# HVBoard.net
KiCad netlist of a schematic drawn in EAGLE
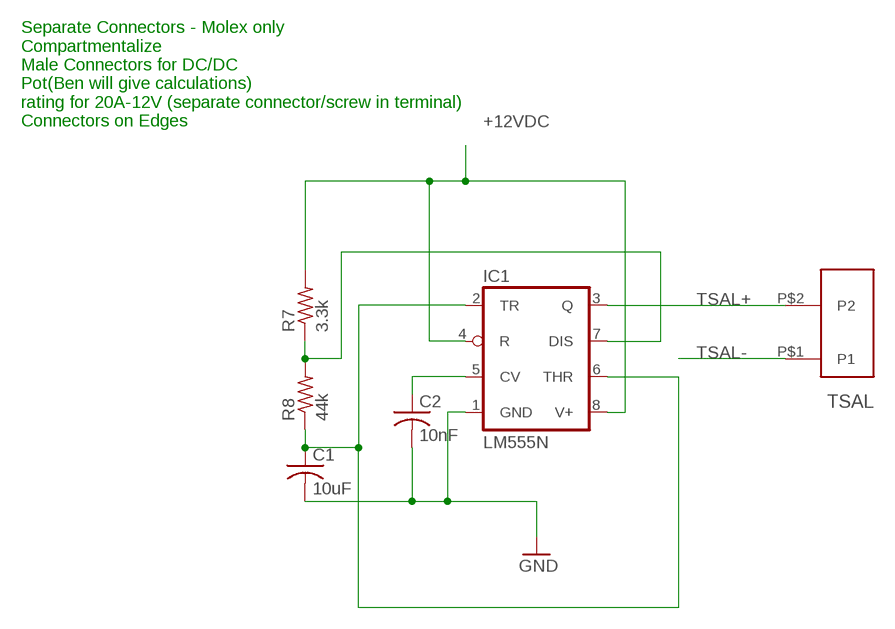
[diagram p0: schematic, sheet 1]
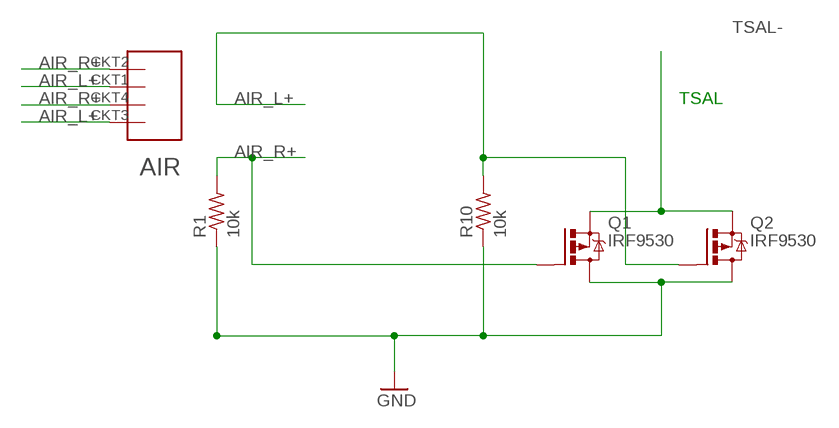
[diagram p1: schematic, sheet 2]
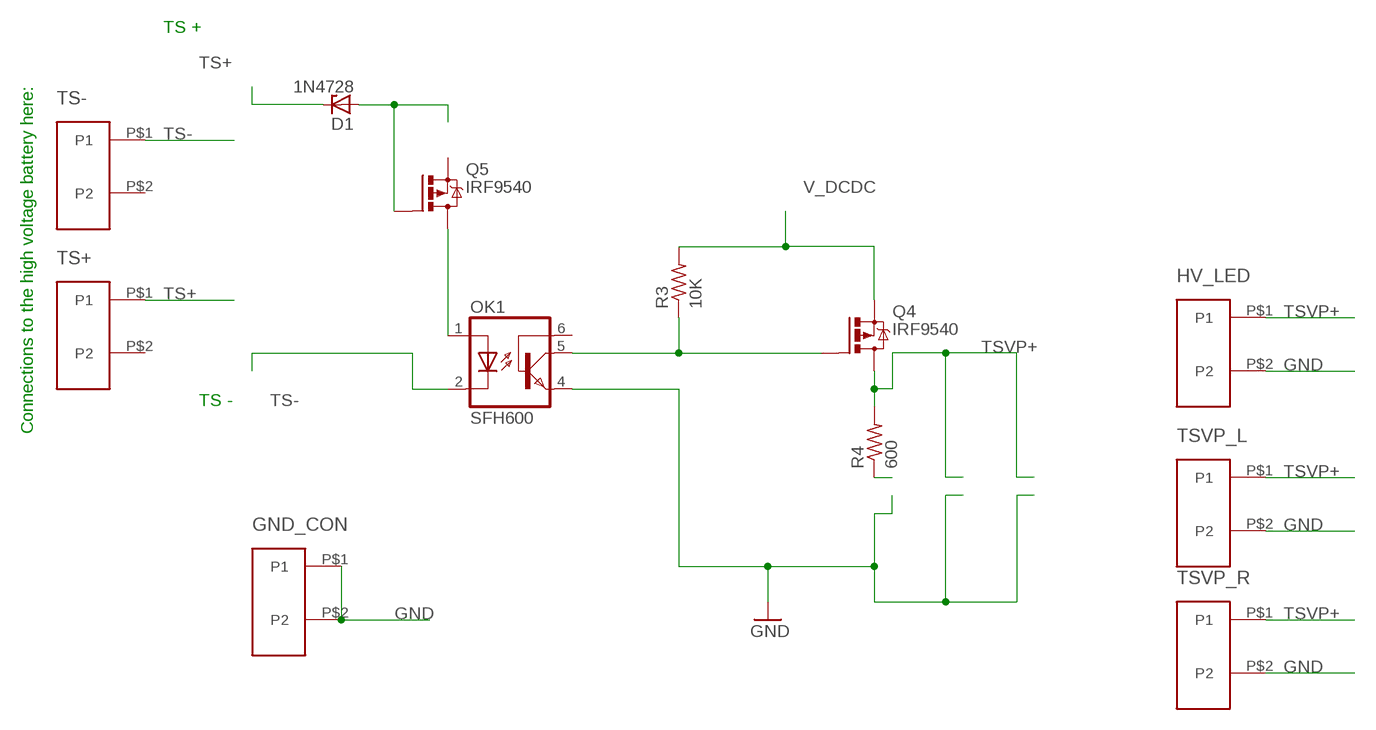
[diagram p2: schematic, sheet 3]
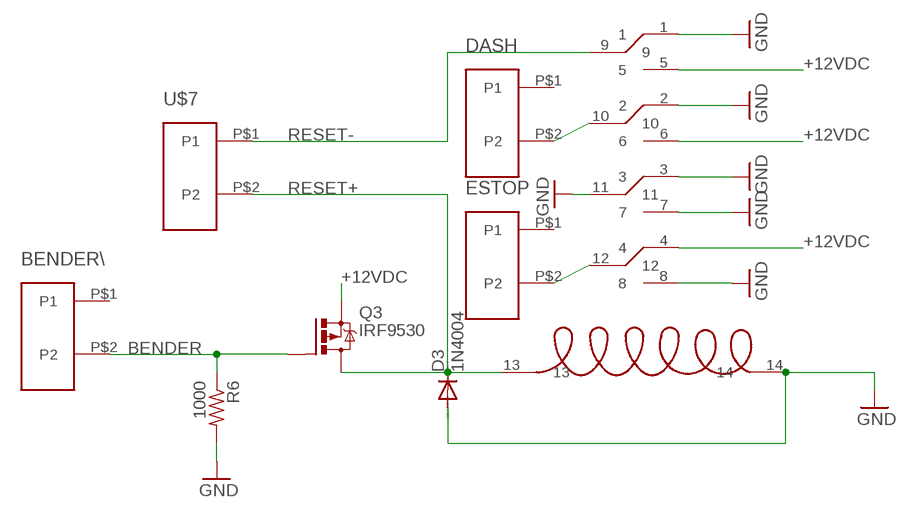
[diagram p3: schematic, sheet 4]
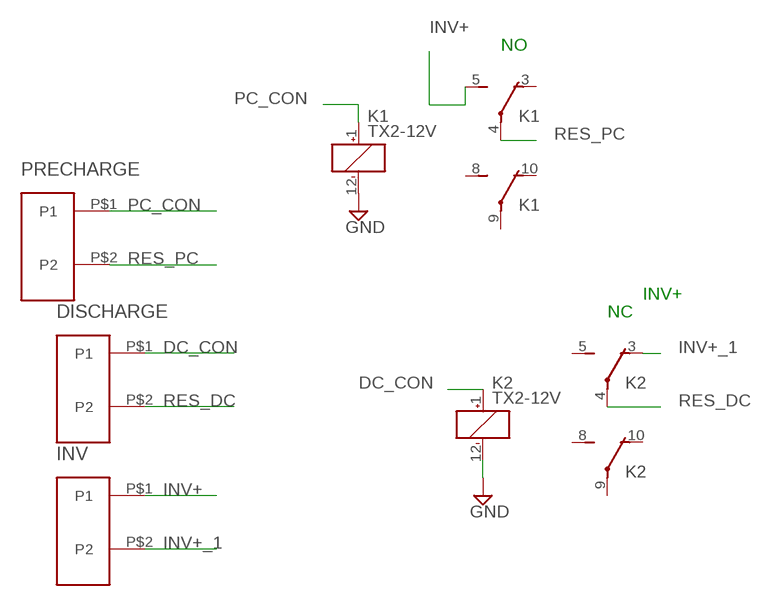
[diagram p4: schematic, sheet 5]
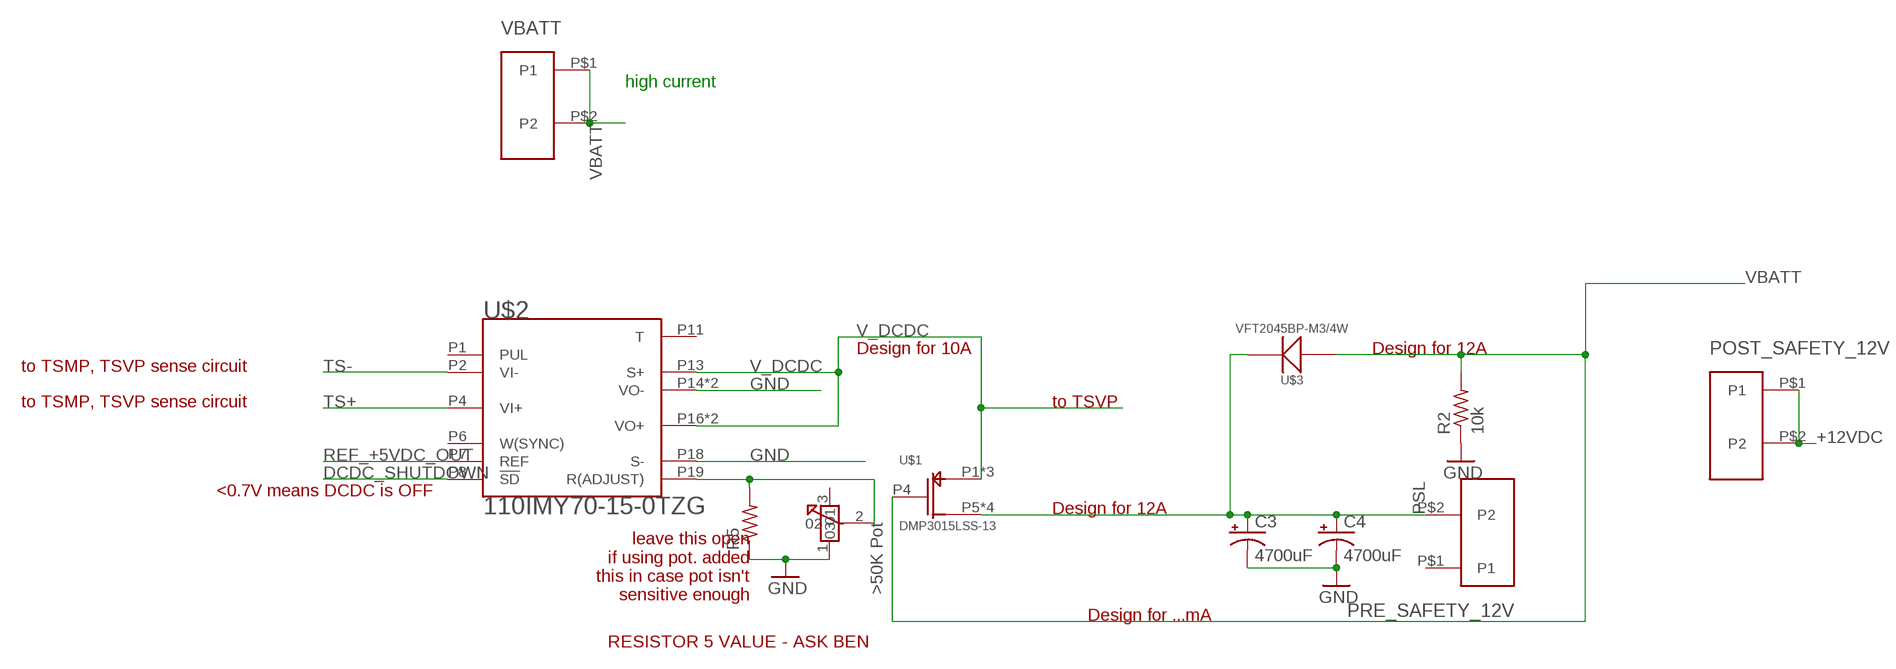
[diagram p5: schematic, sheet 6]

(export (version "E")
  (design (tool "Eeschema 10.0.6"))
  (components
    (comp (ref "BENDER\\")
      (value "MINIFIT_2PIN")
      (footprint "eagle-import:2PIN_MOLEXMINIFIT")
      (libsource (lib "eagle-import") (part "MINIFIT_2PIN"))
    )
    (comp (ref "D3")
      (value "1N4004")
      (footprint "eagle-import:DO41-10")
      (libsource (lib "eagle-import") (part "1N4004"))
    )
    (comp (ref "DASH")
      (value "MINIFIT_2PIN")
      (footprint "eagle-import:2PIN_MOLEXMINIFIT")
      (libsource (lib "eagle-import") (part "MINIFIT_2PIN"))
    )
    (comp (ref "ESTOP")
      (value "MINIFIT_2PIN")
      (footprint "eagle-import:2PIN_MOLEXMINIFIT")
      (libsource (lib "eagle-import") (part "MINIFIT_2PIN"))
    )
    (comp (ref "NEW??1")
      (value "HJ4-DC12VHJ4-DC12V")
      (footprint "eagle-import:HJ4-DC12V")
      (libsource (lib "eagle-import") (part "HJ4-DC12VHJ4-DC12V"))
    )
    (comp (ref "Q3")
      (value "IRF9530")
      (footprint "eagle-import:TO220BV")
      (libsource (lib "eagle-import") (part "IRF9530"))
    )
    (comp (ref "R6")
      (value "1000")
      (footprint "eagle-import:M5923")
      (libsource (lib "eagle-import") (part "R-US_M5923"))
    )
    (comp (ref "U$7")
      (value "MINIFIT_2PIN")
      (footprint "eagle-import:2PIN_MOLEXMINIFIT")
      (libsource (lib "eagle-import") (part "MINIFIT_2PIN"))
    )
    (comp (ref "DISCHARGE")
      (value "MINIFIT_2PIN")
      (footprint "eagle-import:2PIN_MOLEXMINIFIT")
      (libsource (lib "eagle-import") (part "MINIFIT_2PIN"))
    )
    (comp (ref "INV")
      (value "MINIFIT_2PIN")
      (footprint "eagle-import:2PIN_MOLEXMINIFIT")
      (libsource (lib "eagle-import") (part "MINIFIT_2PIN"))
    )
    (comp (ref "K1")
      (value "TX2-12V")
      (footprint "eagle-import:TX2")
      (fields (field (name "MF") "AROMAT/ MATSUSHITA"))
      (libsource (lib "eagle-import") (part "TX2?-12V"))
    )
    (comp (ref "K2")
      (value "TX2-12V")
      (footprint "eagle-import:TX2")
      (fields (field (name "MF") "AROMAT/ MATSUSHITA"))
      (libsource (lib "eagle-import") (part "TX2?-12V"))
    )
    (comp (ref "PRECHARGE")
      (value "MINIFIT_2PIN")
      (footprint "eagle-import:2PIN_MOLEXMINIFIT")
      (libsource (lib "eagle-import") (part "MINIFIT_2PIN"))
    )
    (comp (ref "C3")
      (value "4700uF")
      (footprint "eagle-import:CPOL-RADIAL-1000UF-63V")
      (libsource (lib "eagle-import") (part "CAP_POLPTH3"))
    )
    (comp (ref "C4")
      (value "4700uF")
      (footprint "eagle-import:CPOL-RADIAL-1000UF-63V")
      (libsource (lib "eagle-import") (part "CAP_POLPTH3"))
    )
    (comp (ref "POST_SAFETY_12V")
      (value "MINIFIT_2PIN")
      (footprint "eagle-import:2PIN_MOLEXMINIFIT")
      (libsource (lib "eagle-import") (part "MINIFIT_2PIN"))
    )
    (comp (ref "POT1")
      (value "3310P-001-503L-NP")
      (footprint "eagle-import:3310P-001-503L-NP")
      (libsource (lib "eagle-import") (part "3310P-001-503L-NP"))
    )
    (comp (ref "PRE_SAFETY_12V")
      (value "MINIFIT_2PIN")
      (footprint "eagle-import:2PIN_MOLEXMINIFIT")
      (libsource (lib "eagle-import") (part "MINIFIT_2PIN"))
    )
    (comp (ref "R2")
      (value "10k")
      (footprint "eagle-import:R0603")
      (libsource (lib "eagle-import") (part "resistor_R-US_R0603"))
    )
    (comp (ref "R5")
      (value "R-US_R0805")
      (footprint "eagle-import:R0805")
      (libsource (lib "eagle-import") (part "R-US_R0805"))
    )
    (comp (ref "U$1")
      (value "DMP3015LSS-13")
      (footprint "eagle-import:8-SOP")
      (fields (field (name "MANUFACTURER") "Diodes Incorporated"))
      (libsource (lib "eagle-import") (part "DMP3015LSS-13"))
    )
    (comp (ref "U$2")
      (value "110IMY70-15-0TZG")
      (footprint "eagle-import:110IMY70-15-0TZG")
      (libsource (lib "eagle-import") (part "110IMY70-15-0TZG"))
    )
    (comp (ref "U$3")
      (value "VFT2045BP-M3/4W")
      (footprint "eagle-import:VFT2045BP-M3_4W")
      (fields (field (name "MANUFACTURER") "Vishay Semiconductor Diodes Division"))
      (libsource (lib "eagle-import") (part "VFT2045BP-M3/4W"))
    )
    (comp (ref "VBATT")
      (value "MINIFIT_2PIN")
      (footprint "eagle-import:2PIN_MOLEXMINIFIT")
      (libsource (lib "eagle-import") (part "MINIFIT_2PIN"))
    )
    (comp (ref "C1")
      (value "10uF")
      (footprint "eagle-import:C025-025X050")
      (libsource (lib "eagle-import") (part "C-US025-025X050"))
    )
    (comp (ref "C2")
      (value "10nF")
      (footprint "eagle-import:C025-025X050")
      (libsource (lib "eagle-import") (part "C-US025-025X050"))
    )
    (comp (ref "IC1")
      (value "LM555N")
      (footprint "eagle-import:DIL08")
      (libsource (lib "eagle-import") (part "555NLM"))
    )
    (comp (ref "R7")
      (value "3.3k")
      (footprint "eagle-import:0207_7")
      (libsource (lib "eagle-import") (part "R-US_0207/7"))
    )
    (comp (ref "R8")
      (value "44k")
      (footprint "eagle-import:0207_7")
      (libsource (lib "eagle-import") (part "R-US_0207/7"))
    )
    (comp (ref "TSAL")
      (value "MINIFIT_2PIN")
      (footprint "eagle-import:2PIN_MOLEXMINIFIT")
      (libsource (lib "eagle-import") (part "MINIFIT_2PIN"))
    )
    (comp (ref "D1")
      (value "1N4728")
      (footprint "eagle-import:DO41Z10")
      (libsource (lib "eagle-import") (part "1N4728"))
    )
    (comp (ref "GND_CON")
      (value "MINIFIT_2PIN")
      (footprint "eagle-import:2PIN_MOLEXMINIFIT")
      (libsource (lib "eagle-import") (part "MINIFIT_2PIN"))
    )
    (comp (ref "HV_LED")
      (value "MINIFIT_2PIN")
      (footprint "eagle-import:2PIN_MOLEXMINIFIT")
      (libsource (lib "eagle-import") (part "MINIFIT_2PIN"))
    )
    (comp (ref "OK1")
      (value "SFH600")
      (footprint "eagle-import:DIL06")
      (fields (field (name "MF") "VISHAY/TELEFUNKEN") (field (name "MPN") "SFH600-1"))
      (libsource (lib "eagle-import") (part "SFH600"))
    )
    (comp (ref "Q4")
      (value "IRF9540")
      (footprint "eagle-import:TO220BV")
      (libsource (lib "eagle-import") (part "IRF9530"))
    )
    (comp (ref "Q5")
      (value "IRF9540")
      (footprint "eagle-import:TO220BV")
      (libsource (lib "eagle-import") (part "IRF9530"))
    )
    (comp (ref "R3")
      (value "10K")
      (footprint "eagle-import:R0603")
      (libsource (lib "eagle-import") (part "resistor_R-US_R0603"))
    )
    (comp (ref "R4")
      (value "600")
      (footprint "eagle-import:R0603")
      (libsource (lib "eagle-import") (part "resistor_R-US_R0603"))
    )
    (comp (ref "TS+")
      (value "MINIFIT_2PIN")
      (footprint "eagle-import:2PIN_MOLEXMINIFIT")
      (libsource (lib "eagle-import") (part "MINIFIT_2PIN"))
    )
    (comp (ref "TS-")
      (value "MINIFIT_2PIN")
      (footprint "eagle-import:2PIN_MOLEXMINIFIT")
      (libsource (lib "eagle-import") (part "MINIFIT_2PIN"))
    )
    (comp (ref "TSVP_L")
      (value "MINIFIT_2PIN")
      (footprint "eagle-import:2PIN_MOLEXMINIFIT")
      (libsource (lib "eagle-import") (part "MINIFIT_2PIN"))
    )
    (comp (ref "TSVP_R")
      (value "MINIFIT_2PIN")
      (footprint "eagle-import:2PIN_MOLEXMINIFIT")
      (libsource (lib "eagle-import") (part "MINIFIT_2PIN"))
    )
    (comp (ref "AIR")
      (value "MHYBRIDMOLEX")
      (footprint "eagle-import:MOLEXMINIFIT6")
      (libsource (lib "eagle-import") (part "MHYBRIDMOLEX"))
    )
    (comp (ref "Q1")
      (value "IRF9530")
      (footprint "eagle-import:TO220BV")
      (libsource (lib "eagle-import") (part "IRF9530"))
    )
    (comp (ref "Q2")
      (value "IRF9530")
      (footprint "eagle-import:TO220BV")
      (libsource (lib "eagle-import") (part "IRF9530"))
    )
    (comp (ref "R1")
      (value "10k")
      (footprint "eagle-import:0207_7")
      (libsource (lib "eagle-import") (part "R-US_0207/7"))
    )
    (comp (ref "R10")
      (value "10k")
      (footprint "eagle-import:0207_7")
      (libsource (lib "eagle-import") (part "R-US_0207/7"))
    )
  )
  (nets
    (net (code "1") (name "+12VDC") (class "Default")
      (node (ref "IC1") (pin "4") (pinfunction "R_4") (pintype "input"))
      (node (ref "IC1") (pin "8") (pinfunction "V+_8") (pintype "power_in"))
      (node (ref "NEW??1") (pin "4") (pinfunction "4_4") (pintype "bidirectional"))
      (node (ref "NEW??1") (pin "5") (pinfunction "5_5") (pintype "bidirectional"))
      (node (ref "NEW??1") (pin "6") (pinfunction "6_6") (pintype "bidirectional"))
      (node (ref "POST_SAFETY_12V") (pin "P$1") (pinfunction "P1_P$1") (pintype "bidirectional"))
      (node (ref "POST_SAFETY_12V") (pin "P$2") (pinfunction "P2_P$2") (pintype "bidirectional"))
      (node (ref "Q3") (pin "S") (pinfunction "S_S") (pintype "passive"))
      (node (ref "R7") (pin "2") (pinfunction "2_2") (pintype "passive"))
    )
    (net (code "2") (name "AIR_L+") (class "Default")
      (node (ref "AIR") (pin "CKT1") (pinfunction "GND_CKT1") (pintype "bidirectional"))
      (node (ref "AIR") (pin "CKT3") (pinfunction "V_IN(12)_CKT3") (pintype "bidirectional"))
      (node (ref "Q2") (pin "G") (pinfunction "G_G") (pintype "passive"))
      (node (ref "R10") (pin "2") (pinfunction "2_2") (pintype "passive"))
    )
    (net (code "3") (name "AIR_R+") (class "Default")
      (node (ref "AIR") (pin "CKT2") (pinfunction "GND2_CKT2") (pintype "bidirectional"))
      (node (ref "AIR") (pin "CKT4") (pinfunction "V_IN2(12)_CKT4") (pintype "bidirectional"))
      (node (ref "Q1") (pin "G") (pinfunction "G_G") (pintype "passive"))
      (node (ref "R1") (pin "2") (pinfunction "2_2") (pintype "passive"))
    )
    (net (code "4") (name "BENDER") (class "Default")
      (node (ref "BENDER\\") (pin "P$2") (pinfunction "P2_P$2") (pintype "bidirectional"))
      (node (ref "Q3") (pin "G") (pinfunction "G_G") (pintype "passive"))
      (node (ref "R6") (pin "1") (pinfunction "1_1") (pintype "passive"))
    )
    (net (code "5") (name "DCDC_SHUTDOWN") (class "Default")
      (node (ref "U$2") (pin "P8") (pinfunction "~{SD}_P8") (pintype "bidirectional"))
    )
    (net (code "6") (name "DC_CON") (class "Default")
      (node (ref "DISCHARGE") (pin "P$1") (pinfunction "P1_P$1") (pintype "bidirectional"))
      (node (ref "K2") (pin "1") (pinfunction "+_1") (pintype "passive"))
    )
    (net (code "7") (name "GND") (class "Default")
      (node (ref "C1") (pin "2") (pinfunction "2_2") (pintype "passive"))
      (node (ref "C2") (pin "2") (pinfunction "2_2") (pintype "passive"))
      (node (ref "C3") (pin "2") (pinfunction "-_2") (pintype "passive"))
      (node (ref "C4") (pin "2") (pinfunction "-_2") (pintype "passive"))
      (node (ref "D3") (pin "A") (pinfunction "A_A") (pintype "passive"))
      (node (ref "GND_CON") (pin "P$1") (pinfunction "P1_P$1") (pintype "bidirectional"))
      (node (ref "GND_CON") (pin "P$2") (pinfunction "P2_P$2") (pintype "bidirectional"))
      (node (ref "HV_LED") (pin "P$2") (pinfunction "P2_P$2") (pintype "bidirectional"))
      (node (ref "IC1") (pin "1") (pinfunction "GND_1") (pintype "power_in"))
      (node (ref "K1") (pin "12") (pinfunction "-_12") (pintype "passive"))
      (node (ref "K2") (pin "12") (pinfunction "-_12") (pintype "passive"))
      (node (ref "NEW??1") (pin "1") (pinfunction "1_1") (pintype "bidirectional"))
      (node (ref "NEW??1") (pin "11") (pinfunction "11_11") (pintype "bidirectional"))
      (node (ref "NEW??1") (pin "14") (pinfunction "14_14") (pintype "bidirectional"))
      (node (ref "NEW??1") (pin "2") (pinfunction "2_2") (pintype "bidirectional"))
      (node (ref "NEW??1") (pin "3") (pinfunction "3_3") (pintype "bidirectional"))
      (node (ref "NEW??1") (pin "7") (pinfunction "7_7") (pintype "bidirectional"))
      (node (ref "NEW??1") (pin "8") (pinfunction "8_8") (pintype "bidirectional"))
      (node (ref "OK1") (pin "4") (pinfunction "EMI_4") (pintype "passive"))
      (node (ref "POT1") (pin "1") (pinfunction "01_1") (pintype "bidirectional"))
      (node (ref "Q1") (pin "D") (pinfunction "D_D") (pintype "passive"))
      (node (ref "Q2") (pin "D") (pinfunction "D_D") (pintype "passive"))
      (node (ref "R1") (pin "1") (pinfunction "1_1") (pintype "passive"))
      (node (ref "R10") (pin "1") (pinfunction "1_1") (pintype "passive"))
      (node (ref "R2") (pin "1") (pinfunction "1_1") (pintype "passive"))
      (node (ref "R5") (pin "1") (pinfunction "1_1") (pintype "passive"))
      (node (ref "R6") (pin "2") (pinfunction "2_2") (pintype "passive"))
      (node (ref "TSVP_L") (pin "P$2") (pinfunction "P2_P$2") (pintype "bidirectional"))
      (node (ref "TSVP_R") (pin "P$2") (pinfunction "P2_P$2") (pintype "bidirectional"))
      (node (ref "U$2") (pin "P14") (pinfunction "VO-_P14") (pintype "bidirectional"))
      (node (ref "U$2") (pin "P15") (pinfunction "VO-_P15") (pintype "bidirectional"))
      (node (ref "U$2") (pin "P18") (pinfunction "S-_P18") (pintype "bidirectional"))
    )
    (net (code "8") (name "INV+") (class "Default")
      (node (ref "INV") (pin "P$1") (pinfunction "P1_P$1") (pintype "bidirectional"))
      (node (ref "K1") (pin "5") (pinfunction "S_5") (pintype "passive"))
    )
    (net (code "9") (name "INV+_1") (class "Default")
      (node (ref "INV") (pin "P$2") (pinfunction "P2_P$2") (pintype "bidirectional"))
      (node (ref "K2") (pin "3") (pinfunction "O_3") (pintype "passive"))
    )
    (net (code "10") (name "Net-(D1-PadA)") (class "Default")
      (node (ref "D1") (pin "A") (pinfunction "A_A") (pintype "passive"))
      (node (ref "Q5") (pin "G") (pinfunction "G_G") (pintype "passive"))
    )
    (net (code "11") (name "Net-(DASH-P2)") (class "Default")
      (node (ref "DASH") (pin "P$2") (pinfunction "P2_P$2") (pintype "bidirectional"))
      (node (ref "NEW??1") (pin "10") (pinfunction "10_10") (pintype "bidirectional"))
    )
    (net (code "12") (name "Net-(ESTOP-P2)") (class "Default")
      (node (ref "ESTOP") (pin "P$2") (pinfunction "P2_P$2") (pintype "bidirectional"))
      (node (ref "NEW??1") (pin "12") (pinfunction "12_12") (pintype "bidirectional"))
    )
    (net (code "13") (name "Net-(IC1-CV)") (class "Default")
      (node (ref "C2") (pin "1") (pinfunction "1_1") (pintype "passive"))
      (node (ref "IC1") (pin "5") (pinfunction "CV_5") (pintype "input"))
    )
    (net (code "14") (name "Net-(IC1-DIS)") (class "Default")
      (node (ref "IC1") (pin "7") (pinfunction "DIS_7") (pintype "input"))
      (node (ref "R7") (pin "1") (pinfunction "1_1") (pintype "passive"))
      (node (ref "R8") (pin "2") (pinfunction "2_2") (pintype "passive"))
    )
    (net (code "15") (name "Net-(IC1-THR)") (class "Default")
      (node (ref "C1") (pin "1") (pinfunction "1_1") (pintype "passive"))
      (node (ref "IC1") (pin "2") (pinfunction "TR_2") (pintype "input"))
      (node (ref "IC1") (pin "6") (pinfunction "THR_6") (pintype "input"))
      (node (ref "R8") (pin "1") (pinfunction "1_1") (pintype "passive"))
    )
    (net (code "16") (name "Net-(OK1-A)") (class "Default")
      (node (ref "OK1") (pin "1") (pinfunction "A_1") (pintype "passive"))
      (node (ref "Q5") (pin "D") (pinfunction "D_D") (pintype "passive"))
    )
    (net (code "17") (name "Net-(OK1-COL)") (class "Default")
      (node (ref "OK1") (pin "5") (pinfunction "COL_5") (pintype "passive"))
      (node (ref "Q4") (pin "G") (pinfunction "G_G") (pintype "passive"))
      (node (ref "R3") (pin "1") (pinfunction "1_1") (pintype "passive"))
    )
    (net (code "18") (name "Net-(POT1-02)") (class "Default")
      (node (ref "POT1") (pin "2") (pinfunction "02_2") (pintype "bidirectional"))
      (node (ref "R5") (pin "2") (pinfunction "2_2") (pintype "passive"))
      (node (ref "U$2") (pin "P19") (pinfunction "R(ADJUST)_P19") (pintype "bidirectional"))
    )
    (net (code "19") (name "PC_CON") (class "Default")
      (node (ref "K1") (pin "1") (pinfunction "+_1") (pintype "passive"))
      (node (ref "PRECHARGE") (pin "P$1") (pinfunction "P1_P$1") (pintype "bidirectional"))
    )
    (net (code "20") (name "PSL") (class "Default")
      (node (ref "C3") (pin "1") (pinfunction "+_1") (pintype "passive"))
      (node (ref "C4") (pin "1") (pinfunction "+_1") (pintype "passive"))
      (node (ref "PRE_SAFETY_12V") (pin "P$2") (pinfunction "P2_P$2") (pintype "bidirectional"))
      (node (ref "U$1") (pin "P5") (pinfunction "D_P5") (pintype "bidirectional"))
      (node (ref "U$1") (pin "P6") (pinfunction "D_P6") (pintype "bidirectional"))
      (node (ref "U$1") (pin "P7") (pinfunction "D_P7") (pintype "bidirectional"))
      (node (ref "U$1") (pin "P8") (pinfunction "D_P8") (pintype "bidirectional"))
      (node (ref "U$3") (pin "P2") (pinfunction "P2_P2") (pintype "bidirectional"))
    )
    (net (code "21") (name "REF_+5VDC_OUT") (class "Default")
      (node (ref "U$2") (pin "P7") (pinfunction "REF_P7") (pintype "bidirectional"))
    )
    (net (code "22") (name "RESET+") (class "Default")
      (node (ref "D3") (pin "C") (pinfunction "C_C") (pintype "passive"))
      (node (ref "NEW??1") (pin "13") (pinfunction "13_13") (pintype "bidirectional"))
      (node (ref "Q3") (pin "D") (pinfunction "D_D") (pintype "passive"))
      (node (ref "U$7") (pin "P$2") (pinfunction "P2_P$2") (pintype "bidirectional"))
    )
    (net (code "23") (name "RESET-") (class "Default")
      (node (ref "NEW??1") (pin "9") (pinfunction "9_9") (pintype "bidirectional"))
      (node (ref "U$7") (pin "P$1") (pinfunction "P1_P$1") (pintype "bidirectional"))
    )
    (net (code "24") (name "RES_DC") (class "Default")
      (node (ref "DISCHARGE") (pin "P$2") (pinfunction "P2_P$2") (pintype "bidirectional"))
      (node (ref "K2") (pin "4") (pinfunction "P_4") (pintype "passive"))
    )
    (net (code "25") (name "RES_PC") (class "Default")
      (node (ref "K1") (pin "4") (pinfunction "P_4") (pintype "passive"))
      (node (ref "PRECHARGE") (pin "P$2") (pinfunction "P2_P$2") (pintype "bidirectional"))
    )
    (net (code "26") (name "TS+") (class "Default")
      (node (ref "D1") (pin "C") (pinfunction "C_C") (pintype "passive"))
      (node (ref "TS+") (pin "P$1") (pinfunction "P1_P$1") (pintype "bidirectional"))
      (node (ref "U$2") (pin "P4") (pinfunction "VI+_P4") (pintype "bidirectional"))
    )
    (net (code "27") (name "TS-") (class "Default")
      (node (ref "OK1") (pin "2") (pinfunction "C_2") (pintype "passive"))
      (node (ref "TS-") (pin "P$1") (pinfunction "P1_P$1") (pintype "bidirectional"))
      (node (ref "U$2") (pin "P2") (pinfunction "VI-_P2") (pintype "bidirectional"))
    )
    (net (code "28") (name "TSAL+") (class "Default")
      (node (ref "IC1") (pin "3") (pinfunction "Q_3") (pintype "output"))
      (node (ref "TSAL") (pin "P$2") (pinfunction "P2_P$2") (pintype "bidirectional"))
    )
    (net (code "29") (name "TSAL-") (class "Default")
      (node (ref "Q1") (pin "S") (pinfunction "S_S") (pintype "passive"))
      (node (ref "Q2") (pin "S") (pinfunction "S_S") (pintype "passive"))
      (node (ref "TSAL") (pin "P$1") (pinfunction "P1_P$1") (pintype "bidirectional"))
    )
    (net (code "30") (name "TSVP+") (class "Default")
      (node (ref "HV_LED") (pin "P$1") (pinfunction "P1_P$1") (pintype "bidirectional"))
      (node (ref "Q4") (pin "D") (pinfunction "D_D") (pintype "passive"))
      (node (ref "R4") (pin "2") (pinfunction "2_2") (pintype "passive"))
      (node (ref "TSVP_L") (pin "P$1") (pinfunction "P1_P$1") (pintype "bidirectional"))
      (node (ref "TSVP_R") (pin "P$1") (pinfunction "P1_P$1") (pintype "bidirectional"))
    )
    (net (code "31") (name "VBATT") (class "Default")
      (node (ref "R2") (pin "2") (pinfunction "2_2") (pintype "passive"))
      (node (ref "U$1") (pin "P4") (pinfunction "G_P4") (pintype "bidirectional"))
      (node (ref "U$3") (pin "P1") (pinfunction "P1_P1") (pintype "bidirectional"))
      (node (ref "VBATT") (pin "P$1") (pinfunction "P1_P$1") (pintype "bidirectional"))
      (node (ref "VBATT") (pin "P$2") (pinfunction "P2_P$2") (pintype "bidirectional"))
    )
    (net (code "32") (name "V_DCDC") (class "Default")
      (node (ref "Q4") (pin "S") (pinfunction "S_S") (pintype "passive"))
      (node (ref "R3") (pin "2") (pinfunction "2_2") (pintype "passive"))
      (node (ref "U$1") (pin "P1") (pinfunction "S_P1") (pintype "bidirectional"))
      (node (ref "U$1") (pin "P2") (pinfunction "S_P2") (pintype "bidirectional"))
      (node (ref "U$1") (pin "P3") (pinfunction "S_P3") (pintype "bidirectional"))
      (node (ref "U$2") (pin "P13") (pinfunction "S+_P13") (pintype "bidirectional"))
      (node (ref "U$2") (pin "P16") (pinfunction "VO+_P16") (pintype "bidirectional"))
      (node (ref "U$2") (pin "P17") (pinfunction "VO+_P17") (pintype "bidirectional"))
    )
    (net (code "33") (name "unconnected-(BENDER\\-P1-PadP$1)") (class "Default")
      (node (ref "BENDER\\") (pin "P$1") (pinfunction "P1_P$1") (pintype "bidirectional"))
    )
    (net (code "34") (name "unconnected-(DASH-P1-PadP$1)") (class "Default")
      (node (ref "DASH") (pin "P$1") (pinfunction "P1_P$1") (pintype "bidirectional"))
    )
    (net (code "35") (name "unconnected-(ESTOP-P1-PadP$1)") (class "Default")
      (node (ref "ESTOP") (pin "P$1") (pinfunction "P1_P$1") (pintype "bidirectional"))
    )
    (net (code "36") (name "unconnected-(K1A-O-Pad3)") (class "Default")
      (node (ref "K1") (pin "3") (pinfunction "O_3") (pintype "passive"))
    )
    (net (code "37") (name "unconnected-(K1B-O-Pad10)") (class "Default")
      (node (ref "K1") (pin "10") (pinfunction "O_10") (pintype "passive"))
    )
    (net (code "38") (name "unconnected-(K1B-P-Pad9)") (class "Default")
      (node (ref "K1") (pin "9") (pinfunction "P_9") (pintype "passive"))
    )
    (net (code "39") (name "unconnected-(K1B-S-Pad8)") (class "Default")
      (node (ref "K1") (pin "8") (pinfunction "S_8") (pintype "passive"))
    )
    (net (code "40") (name "unconnected-(K2A-S-Pad5)") (class "Default")
      (node (ref "K2") (pin "5") (pinfunction "S_5") (pintype "passive"))
    )
    (net (code "41") (name "unconnected-(K2B-O-Pad10)") (class "Default")
      (node (ref "K2") (pin "10") (pinfunction "O_10") (pintype "passive"))
    )
    (net (code "42") (name "unconnected-(K2B-P-Pad9)") (class "Default")
      (node (ref "K2") (pin "9") (pinfunction "P_9") (pintype "passive"))
    )
    (net (code "43") (name "unconnected-(K2B-S-Pad8)") (class "Default")
      (node (ref "K2") (pin "8") (pinfunction "S_8") (pintype "passive"))
    )
    (net (code "44") (name "unconnected-(OK1-BAS-Pad6)") (class "Default")
      (node (ref "OK1") (pin "6") (pinfunction "BAS_6") (pintype "passive"))
    )
    (net (code "45") (name "unconnected-(POT1-03-Pad3)") (class "Default")
      (node (ref "POT1") (pin "3") (pinfunction "03_3") (pintype "bidirectional"))
    )
    (net (code "46") (name "unconnected-(PRE_SAFETY_12V-P1-PadP$1)") (class "Default")
      (node (ref "PRE_SAFETY_12V") (pin "P$1") (pinfunction "P1_P$1") (pintype "bidirectional"))
    )
    (net (code "47") (name "unconnected-(Q5-PadS)") (class "Default")
      (node (ref "Q5") (pin "S") (pinfunction "S_S") (pintype "passive"))
    )
    (net (code "48") (name "unconnected-(R4-Pad1)") (class "Default")
      (node (ref "R4") (pin "1") (pinfunction "1_1") (pintype "passive"))
    )
    (net (code "49") (name "unconnected-(TS+-P2-PadP$2)") (class "Default")
      (node (ref "TS+") (pin "P$2") (pinfunction "P2_P$2") (pintype "bidirectional"))
    )
    (net (code "50") (name "unconnected-(TS--P2-PadP$2)") (class "Default")
      (node (ref "TS-") (pin "P$2") (pinfunction "P2_P$2") (pintype "bidirectional"))
    )
    (net (code "51") (name "unconnected-(U$2-PUL-PadP1)") (class "Default")
      (node (ref "U$2") (pin "P1") (pinfunction "PUL_P1") (pintype "bidirectional"))
    )
    (net (code "52") (name "unconnected-(U$2-T-PadP11)") (class "Default")
      (node (ref "U$2") (pin "P11") (pinfunction "T_P11") (pintype "bidirectional"))
    )
    (net (code "53") (name "unconnected-(U$2-W(SYNC)-PadP6)") (class "Default")
      (node (ref "U$2") (pin "P6") (pinfunction "W(SYNC)_P6") (pintype "bidirectional"))
    )
  )
)
